# POWER.net
KiCad netlist of a schematic drawn in Altium Designer
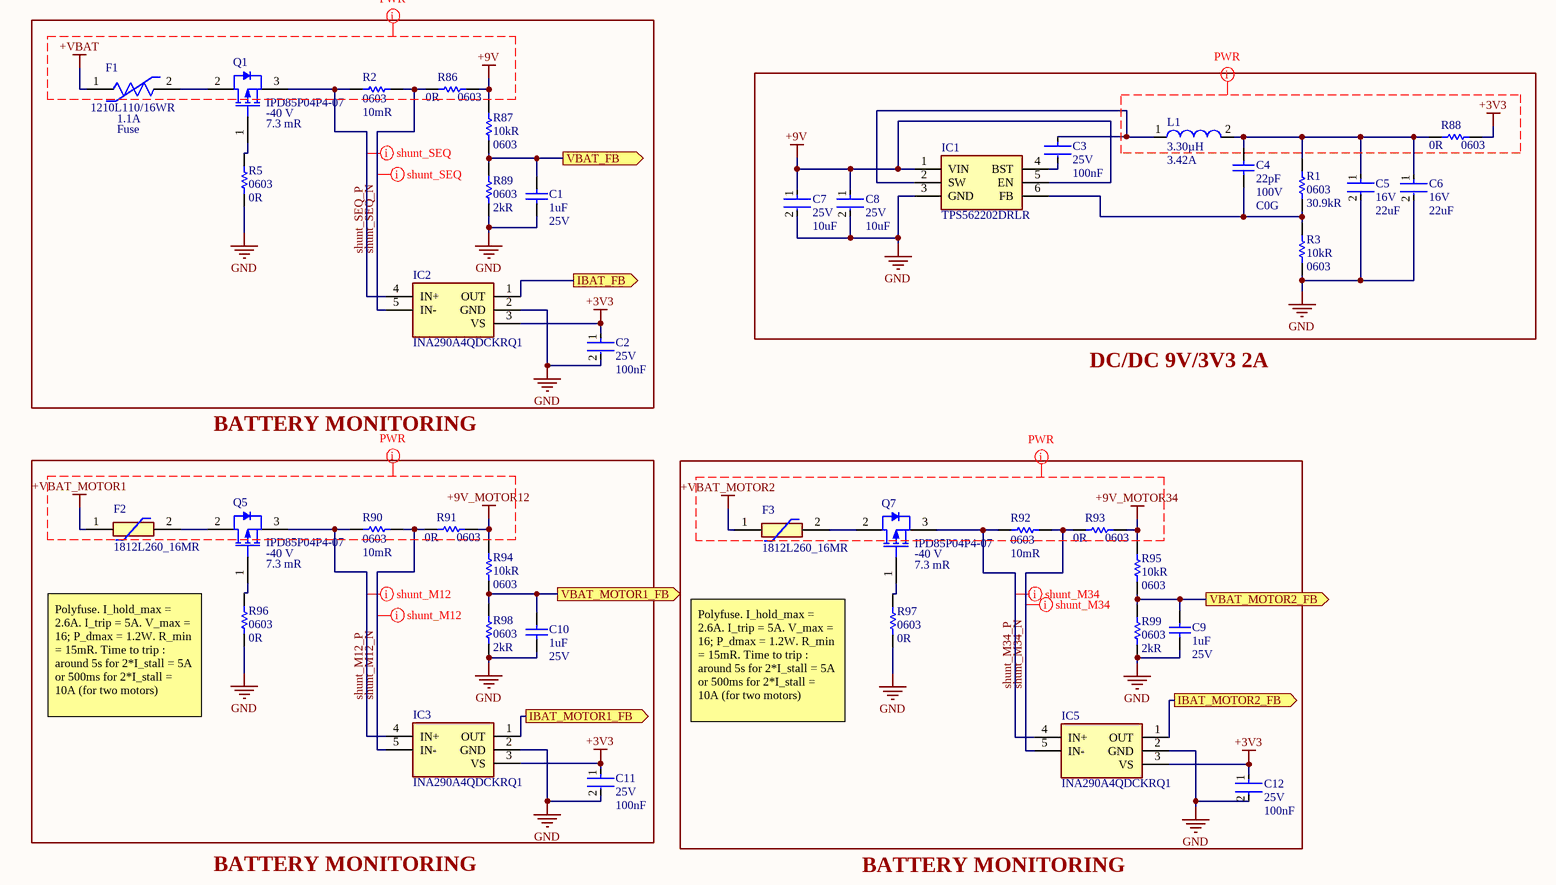
[diagram p0: POWER.SchDoc]

(export (version "E")
  (design (tool "Eeschema 10.0.6"))
  (components
    (comp (ref "C1")
      (value "C0603C105K3PAC7867")
      (footprint "CAPC1608X90X35LL15T15")
      (fields
        (field (name "MANUFACTURER") "Kemet")
        (field (name "MANUFACTURER PART NUMBER") "C0603C105K3PACTU")
        (field (name "CAPACITANCE") "1uF")
        (field (name "TOLERANCE") "10%")
        (field (name "VOLTAGE RATING (DC)") "25V")
      )
      (libsource (lib "Altium Content Vault") (part "CAP"))
    )
    (comp (ref "C2")
      (value "CGA3E2X7R1E104K080AA")
      (footprint "FP-CGA3E-0_3-0_1-MFG")
      (description "Cap Ceramic 100nF 25V X7R 10% Pad SMD 0603 +125°C Automotive T/R")
      (fields
        (field (name "VOLTAGE RATING (DC)") "25V")
        (field (name "CAPACITANCE") "100nF")
        (field (name "TOLERANCE") "10%")
        (field (name "MANUFACTURER") "TDK")
      )
      (libsource (lib "Altium Content Vault") (part "b4654b650e69147ec39a6b967a45e02"))
    )
    (comp (ref "C3")
      (value "CGA3E2X7R1E104K080AA")
      (footprint "FP-CGA3E-0_3-0_1-MFG")
      (description "Cap Ceramic 100nF 25V X7R 10% Pad SMD 0603 +125°C Automotive T/R")
      (fields
        (field (name "VOLTAGE RATING (DC)") "25V")
        (field (name "CAPACITANCE") "100nF")
        (field (name "TOLERANCE") "10%")
        (field (name "MANUFACTURER") "TDK")
      )
      (libsource (lib "") (part "b4654b650e69147ec39a6b967a45e02_1"))
    )
    (comp (ref "C4")
      (value "GRM1885C2A220JA01D")
      (footprint "CAPC1608X90X35NL10T15")
      (fields
        (field (name "MANUFACTURER") "Murata")
        (field (name "CAPACITANCE") "22pF")
        (field (name "TOLERANCE") "5%")
        (field (name "VOLTAGE RATING (DC)") "100V")
        (field (name "DIELECTRIC") "C0G")
        (field (name "VOLTAGE") "100V")
      )
      (libsource (lib "Altium Content Vault") (part "CAP"))
    )
    (comp (ref "C5")
      (value "C2012X5R1C226K125AC")
      (footprint "FP-C2012-125-MFG")
      (description "CAP CER 22UF 16V X5R 0805")
      (fields
        (field (name "MANUFACTURER") "TDK")
        (field (name "OCTOPART") "https://octopart.com/c2012x5r1c226k125ac-tdk-25947713")
        (field (name "VOLTAGE RATING") "16V")
        (field (name "CAPACITANCE") "22uF")
      )
      (libsource (lib "Altium Content Vault") (part "11868f565c42a9108669ba33697ecf6"))
    )
    (comp (ref "C6")
      (value "C2012X5R1C226K125AC")
      (footprint "FP-C2012-125-MFG")
      (description "CAP CER 22UF 16V X5R 0805")
      (fields
        (field (name "MANUFACTURER") "TDK")
        (field (name "OCTOPART") "https://octopart.com/c2012x5r1c226k125ac-tdk-25947713")
        (field (name "VOLTAGE RATING") "16V")
        (field (name "CAPACITANCE") "22uF")
      )
      (libsource (lib "Altium Content Vault") (part "11868f565c42a9108669ba33697ecf6"))
    )
    (comp (ref "C7")
      (value "C2012X5R1E106K125AB")
      (footprint "FP-C2012-125-0_2-IPC_B")
      (description "Multilayer Ceramic Capacitors 10μF ±10% 25V X5R SMD 0805")
      (fields
        (field (name "VOLTAGE") "25V")
        (field (name "VOLTAGE RATING (DC)") "25V")
        (field (name "TOLERANCE") "10%")
        (field (name "CAPACITANCE") "10uF")
      )
      (libsource (lib "Altium Content Vault") (part "b4654b650e69147ec39a6b967a45e02"))
    )
    (comp (ref "C8")
      (value "C2012X5R1E106K125AB")
      (footprint "FP-C2012-125-0_2-IPC_B")
      (description "Multilayer Ceramic Capacitors 10μF ±10% 25V X5R SMD 0805")
      (fields
        (field (name "VOLTAGE") "25V")
        (field (name "VOLTAGE RATING (DC)") "25V")
        (field (name "TOLERANCE") "10%")
        (field (name "CAPACITANCE") "10uF")
      )
      (libsource (lib "Altium Content Vault") (part "b4654b650e69147ec39a6b967a45e02"))
    )
    (comp (ref "C9")
      (value "C0603C105K3PAC7867")
      (footprint "CAPC1608X90X35LL15T15")
      (fields
        (field (name "MANUFACTURER") "Kemet")
        (field (name "MANUFACTURER PART NUMBER") "C0603C105K3PACTU")
        (field (name "CAPACITANCE") "1uF")
        (field (name "TOLERANCE") "10%")
        (field (name "VOLTAGE RATING (DC)") "25V")
      )
      (libsource (lib "Altium Content Vault") (part "CAP"))
    )
    (comp (ref "C10")
      (value "C0603C105K3PAC7867")
      (footprint "CAPC1608X90X35LL15T15")
      (fields
        (field (name "MANUFACTURER") "Kemet")
        (field (name "MANUFACTURER PART NUMBER") "C0603C105K3PACTU")
        (field (name "CAPACITANCE") "1uF")
        (field (name "TOLERANCE") "10%")
        (field (name "VOLTAGE RATING (DC)") "25V")
      )
      (libsource (lib "Altium Content Vault") (part "CAP"))
    )
    (comp (ref "C11")
      (value "CGA3E2X7R1E104K080AA")
      (footprint "FP-CGA3E-0_3-0_1-MFG")
      (description "Cap Ceramic 100nF 25V X7R 10% Pad SMD 0603 +125°C Automotive T/R")
      (fields
        (field (name "VOLTAGE RATING (DC)") "25V")
        (field (name "CAPACITANCE") "100nF")
        (field (name "TOLERANCE") "10%")
        (field (name "MANUFACTURER") "TDK")
      )
      (libsource (lib "Altium Content Vault") (part "b4654b650e69147ec39a6b967a45e02"))
    )
    (comp (ref "C12")
      (value "CGA3E2X7R1E104K080AA")
      (footprint "FP-CGA3E-0_3-0_1-MFG")
      (description "Cap Ceramic 100nF 25V X7R 10% Pad SMD 0603 +125°C Automotive T/R")
      (fields
        (field (name "VOLTAGE RATING (DC)") "25V")
        (field (name "CAPACITANCE") "100nF")
        (field (name "TOLERANCE") "10%")
        (field (name "MANUFACTURER") "TDK")
      )
      (libsource (lib "Altium Content Vault") (part "b4654b650e69147ec39a6b967a45e02"))
    )
    (comp (ref "F1")
      (value "1210L110/16WR")
      (footprint "FP-1210L110-16WR-MFG")
      (description "PTC RESET FUSE 16V 1.1A 1210")
      (fields
        (field (name "HOLD CURRENT") "1.1A")
        (field (name "CATEGORY") "Fuse")
        (field (name "OCTOPART") "https://octopart.com/1210l110%2F16wr-littelfuse-28867107")
        (field (name "MANUFACTURER") "Littelfuse Inc")
      )
      (libsource (lib "Altium Content Vault") (part "1c6d77a0208143737455a0c7eb396be"))
    )
    (comp (ref "F2")
      (value "1812L260_16MR")
      (footprint "SamacSys:1812L010DR")
      (description "Resettable Fuse")
      (fields
        (field (name "MANUFACTURER_PART_NUMBER") "1812L260/16MR")
        (field (name "MOUSER PART NUMBER") "576-1812L260/16MR")
      )
      (libsource (lib "*") (part "1812L260_16MR"))
    )
    (comp (ref "F3")
      (value "1812L260_16MR")
      (footprint "SamacSys:1812L010DR")
      (description "Resettable Fuse")
      (fields
        (field (name "MANUFACTURER_PART_NUMBER") "1812L260/16MR")
        (field (name "MOUSER PART NUMBER") "576-1812L260/16MR")
      )
      (libsource (lib "*") (part "1812L260_16MR"))
    )
    (comp (ref "IC1")
      (value "TPS562202DRLR")
      (footprint "SamacSys:SOTFL50P160X60-6N")
      (description "Integrated Circuit")
      (fields (field (name "MOUSER PART NUMBER") "595-TPS562202DRLR"))
      (libsource (lib "*") (part "TPS562202DRLR"))
    )
    (comp (ref "IC2")
      (value "INA290A4QDCKRQ1")
      (footprint "SamacSys:SOT65P210X110-5N")
      (description "Integrated Circuit")
      (fields (field (name "MOUSER PART NUMBER") "595-INA290A4QDCKRQ1"))
      (libsource (lib "*") (part "INA290A4QDCKRQ1"))
    )
    (comp (ref "IC3")
      (value "INA290A4QDCKRQ1")
      (footprint "SamacSys:SOT65P210X110-5N")
      (description "Integrated Circuit")
      (fields (field (name "MOUSER PART NUMBER") "595-INA290A4QDCKRQ1"))
      (libsource (lib "*") (part "INA290A4QDCKRQ1"))
    )
    (comp (ref "IC5")
      (value "INA290A4QDCKRQ1")
      (footprint "SamacSys:SOT65P210X110-5N")
      (description "Integrated Circuit")
      (fields (field (name "MOUSER PART NUMBER") "595-INA290A4QDCKRQ1"))
      (libsource (lib "*") (part "INA290A4QDCKRQ1"))
    )
    (comp (ref "L1")
      (value "7447789003")
      (footprint "WE-PD-S-PB")
      (description "SMD-Shielded Power Inductor WE-PD, L=3.30 µH")
      (fields
        (field (name "INDUCTANCE") "3.30µH")
        (field (name "MANUFACTURER") "Wuerth Elektronik")
        (field (name "TOLERANCE") "20%")
        (field (name "CURRENT RATING") "3.42A")
      )
      (libsource (lib "Altium Content Vault") (part "PAS-IND-INDUCTOR-2"))
    )
    (comp (ref "Q1")
      (value "IPD85P04P4-07")
      (footprint "INF-PG-TO252-3-313_L")
      (description "OptiMOS-P2 Power-Transistor, -40 V VDS, -85 A ID, PG-TO252-3-313, Reel, Green")
      (fields
        (field (name "VDS (MAX)") "-40 V")
        (field (name "RDS (ON) (MAX) (@10V)") "7.3 mR")
        (field (name "MANUFACTURER") "Infineon")
      )
      (libsource (lib "Altium Content Vault") (part "INF-MOSFET-P-3"))
    )
    (comp (ref "Q5")
      (value "IPD85P04P4-07")
      (footprint "INF-PG-TO252-3-313_L")
      (description "OptiMOS-P2 Power-Transistor, -40 V VDS, -85 A ID, PG-TO252-3-313, Reel, Green")
      (fields
        (field (name "VDS (MAX)") "-40 V")
        (field (name "RDS (ON) (MAX) (@10V)") "7.3 mR")
        (field (name "MANUFACTURER") "Infineon")
      )
      (libsource (lib "Altium Content Vault") (part "INF-MOSFET-P-3"))
    )
    (comp (ref "Q7")
      (value "IPD85P04P4-07")
      (footprint "INF-PG-TO252-3-313_L")
      (description "OptiMOS-P2 Power-Transistor, -40 V VDS, -85 A ID, PG-TO252-3-313, Reel, Green")
      (fields
        (field (name "VDS (MAX)") "-40 V")
        (field (name "RDS (ON) (MAX) (@10V)") "7.3 mR")
        (field (name "MANUFACTURER") "Infineon")
      )
      (libsource (lib "Altium Content Vault") (part "INF-MOSFET-P-3"))
    )
    (comp (ref "R1")
      (value "RC0603FR-0730K9L")
      (footprint "RESC1608X55X25NL10T15")
      (fields
        (field (name "MANUFACTURER") "Yageo")
        (field (name "CASE CODE (IMPERIAL)") "0603")
        (field (name "TOLERANCE") "1%")
        (field (name "RESISTANCE") "30.9kR")
      )
      (libsource (lib "Altium Content Vault") (part "RES"))
    )
    (comp (ref "R2")
      (value "WSL0603R0100FEA")
      (footprint "RESC1508X46X38ML25T25")
      (fields
        (field (name "MANUFACTURER") "Vishay Dale")
        (field (name "CASE CODE (IMPERIAL)") "0603")
        (field (name "TOLERANCE") "1%")
        (field (name "RESISTANCE") "10mR")
      )
      (libsource (lib "Altium Content Vault") (part "RES"))
    )
    (comp (ref "R3")
      (value "ERJ3EKF1002V")
      (footprint "RESC1609X55X30LL15T15")
      (description "Chip Resistor, 10 KOhm, +/- 1%, 0.1 W, -55 to 155 degC, 0603 (1608 Metric), RoHS, Tape and Reel")
      (fields
        (field (name "RESISTANCE") "10kR")
        (field (name "CASE CODE (IMPERIAL)") "0603")
        (field (name "TOLERANCE") "1%")
        (field (name "MANUFACTURER") "Panasonic")
      )
      (libsource (lib "Altium Content Vault") (part "RES-2"))
    )
    (comp (ref "R5")
      (value "RC0603JR-070RL")
      (footprint "RESC1608X55X25ML10T15")
      (description "Chip Resistor, 0 Ohm, +/- 5%, 0.1 W, -55 to 155 degC, 0603 (1608 Metric), RoHS, Tape and Reel")
      (fields
        (field (name "TOLERANCE") "5%")
        (field (name "CASE CODE (IMPERIAL)") "0603")
        (field (name "RESISTANCE") "0R")
        (field (name "MANUFACTURER") "Yageo")
      )
      (libsource (lib "Altium Content Vault") (part "RES-2"))
    )
    (comp (ref "R86")
      (value "RC0603JR-070RL")
      (footprint "RESC1608X55X25ML10T15")
      (description "Chip Resistor, 0 Ohm, +/- 5%, 0.1 W, -55 to 155 degC, 0603 (1608 Metric), RoHS, Tape and Reel")
      (fields
        (field (name "TOLERANCE") "5%")
        (field (name "CASE CODE (IMPERIAL)") "0603")
        (field (name "RESISTANCE") "0R")
        (field (name "MANUFACTURER") "Yageo")
      )
      (libsource (lib "Altium Content Vault") (part "RES-2"))
    )
    (comp (ref "R87")
      (value "ERJ3EKF1002V")
      (footprint "RESC1609X55X30LL15T15")
      (description "Chip Resistor, 10 KOhm, +/- 1%, 0.1 W, -55 to 155 degC, 0603 (1608 Metric), RoHS, Tape and Reel")
      (fields
        (field (name "RESISTANCE") "10kR")
        (field (name "CASE CODE (IMPERIAL)") "0603")
        (field (name "TOLERANCE") "1%")
        (field (name "MANUFACTURER") "Panasonic")
      )
      (libsource (lib "Altium Content Vault") (part "RES-2"))
    )
    (comp (ref "R88")
      (value "RC0603JR-070RL")
      (footprint "RESC1608X55X25ML10T15")
      (description "Chip Resistor, 0 Ohm, +/- 5%, 0.1 W, -55 to 155 degC, 0603 (1608 Metric), RoHS, Tape and Reel")
      (fields
        (field (name "TOLERANCE") "5%")
        (field (name "CASE CODE (IMPERIAL)") "0603")
        (field (name "RESISTANCE") "0R")
        (field (name "MANUFACTURER") "Yageo")
      )
      (libsource (lib "Altium Content Vault") (part "RES-2"))
    )
    (comp (ref "R89")
      (value "ERJ-3EKF2001V")
      (footprint "RESC1608X55X30ML15T15")
      (fields
        (field (name "MANUFACTURER") "Panasonic")
        (field (name "CASE CODE (IMPERIAL)") "0603")
        (field (name "RESISTANCE") "2kR")
        (field (name "TOLERANCE") "1%")
      )
      (libsource (lib "Altium Content Vault") (part "RES"))
    )
    (comp (ref "R90")
      (value "WSL0603R0100FEA")
      (footprint "RESC1508X46X38ML25T25")
      (fields
        (field (name "MANUFACTURER") "Vishay Dale")
        (field (name "CASE CODE (IMPERIAL)") "0603")
        (field (name "TOLERANCE") "1%")
        (field (name "RESISTANCE") "10mR")
      )
      (libsource (lib "Altium Content Vault") (part "RES"))
    )
    (comp (ref "R91")
      (value "RC0603JR-070RL")
      (footprint "RESC1608X55X25ML10T15")
      (description "Chip Resistor, 0 Ohm, +/- 5%, 0.1 W, -55 to 155 degC, 0603 (1608 Metric), RoHS, Tape and Reel")
      (fields
        (field (name "TOLERANCE") "5%")
        (field (name "CASE CODE (IMPERIAL)") "0603")
        (field (name "RESISTANCE") "0R")
        (field (name "MANUFACTURER") "Yageo")
      )
      (libsource (lib "Altium Content Vault") (part "RES-2"))
    )
    (comp (ref "R92")
      (value "WSL0603R0100FEA")
      (footprint "RESC1508X46X38ML25T25")
      (fields
        (field (name "MANUFACTURER") "Vishay Dale")
        (field (name "CASE CODE (IMPERIAL)") "0603")
        (field (name "TOLERANCE") "1%")
        (field (name "RESISTANCE") "10mR")
      )
      (libsource (lib "Altium Content Vault") (part "RES"))
    )
    (comp (ref "R93")
      (value "RC0603JR-070RL")
      (footprint "RESC1608X55X25ML10T15")
      (description "Chip Resistor, 0 Ohm, +/- 5%, 0.1 W, -55 to 155 degC, 0603 (1608 Metric), RoHS, Tape and Reel")
      (fields
        (field (name "TOLERANCE") "5%")
        (field (name "CASE CODE (IMPERIAL)") "0603")
        (field (name "RESISTANCE") "0R")
        (field (name "MANUFACTURER") "Yageo")
      )
      (libsource (lib "Altium Content Vault") (part "RES-2"))
    )
    (comp (ref "R94")
      (value "ERJ3EKF1002V")
      (footprint "RESC1609X55X30LL15T15")
      (description "Chip Resistor, 10 KOhm, +/- 1%, 0.1 W, -55 to 155 degC, 0603 (1608 Metric), RoHS, Tape and Reel")
      (fields
        (field (name "RESISTANCE") "10kR")
        (field (name "CASE CODE (IMPERIAL)") "0603")
        (field (name "TOLERANCE") "1%")
        (field (name "MANUFACTURER") "Panasonic")
      )
      (libsource (lib "Altium Content Vault") (part "RES-2"))
    )
    (comp (ref "R95")
      (value "ERJ3EKF1002V")
      (footprint "RESC1609X55X30LL15T15")
      (description "Chip Resistor, 10 KOhm, +/- 1%, 0.1 W, -55 to 155 degC, 0603 (1608 Metric), RoHS, Tape and Reel")
      (fields
        (field (name "RESISTANCE") "10kR")
        (field (name "CASE CODE (IMPERIAL)") "0603")
        (field (name "TOLERANCE") "1%")
        (field (name "MANUFACTURER") "Panasonic")
      )
      (libsource (lib "Altium Content Vault") (part "RES-2"))
    )
    (comp (ref "R96")
      (value "RC0603JR-070RL")
      (footprint "RESC1608X55X25ML10T15")
      (description "Chip Resistor, 0 Ohm, +/- 5%, 0.1 W, -55 to 155 degC, 0603 (1608 Metric), RoHS, Tape and Reel")
      (fields
        (field (name "TOLERANCE") "5%")
        (field (name "CASE CODE (IMPERIAL)") "0603")
        (field (name "RESISTANCE") "0R")
        (field (name "MANUFACTURER") "Yageo")
      )
      (libsource (lib "Altium Content Vault") (part "RES-2"))
    )
    (comp (ref "R97")
      (value "RC0603JR-070RL")
      (footprint "RESC1608X55X25ML10T15")
      (description "Chip Resistor, 0 Ohm, +/- 5%, 0.1 W, -55 to 155 degC, 0603 (1608 Metric), RoHS, Tape and Reel")
      (fields
        (field (name "TOLERANCE") "5%")
        (field (name "CASE CODE (IMPERIAL)") "0603")
        (field (name "RESISTANCE") "0R")
        (field (name "MANUFACTURER") "Yageo")
      )
      (libsource (lib "Altium Content Vault") (part "RES-2"))
    )
    (comp (ref "R98")
      (value "ERJ-3EKF2001V")
      (footprint "RESC1608X55X30ML15T15")
      (fields
        (field (name "MANUFACTURER") "Panasonic")
        (field (name "CASE CODE (IMPERIAL)") "0603")
        (field (name "RESISTANCE") "2kR")
        (field (name "TOLERANCE") "1%")
      )
      (libsource (lib "Altium Content Vault") (part "RES"))
    )
    (comp (ref "R99")
      (value "ERJ-3EKF2001V")
      (footprint "RESC1608X55X30ML15T15")
      (fields
        (field (name "MANUFACTURER") "Panasonic")
        (field (name "CASE CODE (IMPERIAL)") "0603")
        (field (name "RESISTANCE") "2kR")
        (field (name "TOLERANCE") "1%")
      )
      (libsource (lib "Altium Content Vault") (part "RES"))
    )
  )
  (nets
    (net (code "1") (name "+3V3") (class "Default")
      (node (ref "C11") (pin "1") (pinfunction "1_1") (pintype "passive"))
      (node (ref "C12") (pin "1") (pinfunction "1_1") (pintype "passive"))
      (node (ref "C2") (pin "1") (pinfunction "1_1") (pintype "passive"))
      (node (ref "IC2") (pin "3") (pinfunction "VS_3") (pintype "passive"))
      (node (ref "IC3") (pin "3") (pinfunction "VS_3") (pintype "passive"))
      (node (ref "IC5") (pin "3") (pinfunction "VS_3") (pintype "passive"))
      (node (ref "R88") (pin "2") (pinfunction "2_2") (pintype "passive"))
    )
    (net (code "2") (name "+9V") (class "Default")
      (node (ref "C7") (pin "1") (pinfunction "1_1") (pintype "passive"))
      (node (ref "C8") (pin "1") (pinfunction "1_1") (pintype "passive"))
      (node (ref "IC1") (pin "1") (pinfunction "VIN_1") (pintype "passive"))
      (node (ref "IC1") (pin "5") (pinfunction "EN_5") (pintype "passive"))
      (node (ref "R86") (pin "2") (pinfunction "2_2") (pintype "passive"))
      (node (ref "R87") (pin "2") (pinfunction "2_2") (pintype "passive"))
    )
    (net (code "3") (name "+9V_MOTOR12") (class "Default")
      (node (ref "R91") (pin "2") (pinfunction "2_2") (pintype "passive"))
      (node (ref "R94") (pin "2") (pinfunction "2_2") (pintype "passive"))
    )
    (net (code "4") (name "+9V_MOTOR34") (class "Default")
      (node (ref "R93") (pin "2") (pinfunction "2_2") (pintype "passive"))
      (node (ref "R95") (pin "2") (pinfunction "2_2") (pintype "passive"))
    )
    (net (code "5") (name "+VBAT") (class "Default")
      (node (ref "F1") (pin "1") (pinfunction "1_1") (pintype "passive"))
    )
    (net (code "6") (name "+VBAT_MOTOR1") (class "Default")
      (node (ref "F2") (pin "1") (pinfunction "1_1") (pintype "passive"))
    )
    (net (code "7") (name "+VBAT_MOTOR2") (class "Default")
      (node (ref "F3") (pin "1") (pinfunction "1_1") (pintype "passive"))
    )
    (net (code "8") (name "/IBAT_FB") (class "Default")
      (node (ref "IC2") (pin "1") (pinfunction "OUT_1") (pintype "passive"))
    )
    (net (code "9") (name "/IBAT_MOTOR1_FB") (class "Default")
      (node (ref "IC3") (pin "1") (pinfunction "OUT_1") (pintype "passive"))
    )
    (net (code "10") (name "/IBAT_MOTOR2_FB") (class "Default")
      (node (ref "IC5") (pin "1") (pinfunction "OUT_1") (pintype "passive"))
    )
    (net (code "11") (name "/VBAT_FB") (class "Default")
      (node (ref "C1") (pin "2") (pinfunction "2_2") (pintype "passive"))
      (node (ref "R87") (pin "1") (pinfunction "1_1") (pintype "passive"))
      (node (ref "R89") (pin "2") (pinfunction "2_2") (pintype "passive"))
    )
    (net (code "12") (name "/VBAT_MOTOR1_FB") (class "Default")
      (node (ref "C10") (pin "2") (pinfunction "2_2") (pintype "passive"))
      (node (ref "R94") (pin "1") (pinfunction "1_1") (pintype "passive"))
      (node (ref "R98") (pin "2") (pinfunction "2_2") (pintype "passive"))
    )
    (net (code "13") (name "/VBAT_MOTOR2_FB") (class "Default")
      (node (ref "C9") (pin "2") (pinfunction "2_2") (pintype "passive"))
      (node (ref "R95") (pin "1") (pinfunction "1_1") (pintype "passive"))
      (node (ref "R99") (pin "2") (pinfunction "2_2") (pintype "passive"))
    )
    (net (code "14") (name "/shunt_M12_N") (class "Default")
      (node (ref "IC3") (pin "5") (pinfunction "IN-_5") (pintype "passive"))
      (node (ref "R90") (pin "2") (pinfunction "2_2") (pintype "passive"))
      (node (ref "R91") (pin "1") (pinfunction "1_1") (pintype "passive"))
    )
    (net (code "15") (name "/shunt_M12_P") (class "Default")
      (node (ref "IC3") (pin "4") (pinfunction "IN+_4") (pintype "passive"))
      (node (ref "Q5") (pin "3") (pinfunction "SOURCE_3") (pintype "passive"))
      (node (ref "R90") (pin "1") (pinfunction "1_1") (pintype "passive"))
    )
    (net (code "16") (name "/shunt_M34_N") (class "Default")
      (node (ref "IC5") (pin "5") (pinfunction "IN-_5") (pintype "passive"))
      (node (ref "R92") (pin "2") (pinfunction "2_2") (pintype "passive"))
      (node (ref "R93") (pin "1") (pinfunction "1_1") (pintype "passive"))
    )
    (net (code "17") (name "/shunt_M34_P") (class "Default")
      (node (ref "IC5") (pin "4") (pinfunction "IN+_4") (pintype "passive"))
      (node (ref "Q7") (pin "3") (pinfunction "SOURCE_3") (pintype "passive"))
      (node (ref "R92") (pin "1") (pinfunction "1_1") (pintype "passive"))
    )
    (net (code "18") (name "/shunt_SEQ_N") (class "Default")
      (node (ref "IC2") (pin "5") (pinfunction "IN-_5") (pintype "passive"))
      (node (ref "R2") (pin "2") (pinfunction "2_2") (pintype "passive"))
      (node (ref "R86") (pin "1") (pinfunction "1_1") (pintype "passive"))
    )
    (net (code "19") (name "/shunt_SEQ_P") (class "Default")
      (node (ref "IC2") (pin "4") (pinfunction "IN+_4") (pintype "passive"))
      (node (ref "Q1") (pin "3") (pinfunction "SOURCE_3") (pintype "passive"))
      (node (ref "R2") (pin "1") (pinfunction "1_1") (pintype "passive"))
    )
    (net (code "20") (name "GND") (class "Default")
      (node (ref "C1") (pin "1") (pinfunction "1_1") (pintype "passive"))
      (node (ref "C10") (pin "1") (pinfunction "1_1") (pintype "passive"))
      (node (ref "C11") (pin "2") (pinfunction "2_2") (pintype "passive"))
      (node (ref "C12") (pin "2") (pinfunction "2_2") (pintype "passive"))
      (node (ref "C2") (pin "2") (pinfunction "2_2") (pintype "passive"))
      (node (ref "C5") (pin "2") (pinfunction "2_2") (pintype "passive"))
      (node (ref "C6") (pin "2") (pinfunction "2_2") (pintype "passive"))
      (node (ref "C7") (pin "2") (pinfunction "2_2") (pintype "passive"))
      (node (ref "C8") (pin "2") (pinfunction "2_2") (pintype "passive"))
      (node (ref "C9") (pin "1") (pinfunction "1_1") (pintype "passive"))
      (node (ref "IC1") (pin "3") (pinfunction "GND_3") (pintype "passive"))
      (node (ref "IC2") (pin "2") (pinfunction "GND_2") (pintype "passive"))
      (node (ref "IC3") (pin "2") (pinfunction "GND_2") (pintype "passive"))
      (node (ref "IC5") (pin "2") (pinfunction "GND_2") (pintype "passive"))
      (node (ref "R3") (pin "1") (pinfunction "1_1") (pintype "passive"))
      (node (ref "R5") (pin "1") (pinfunction "1_1") (pintype "passive"))
      (node (ref "R89") (pin "1") (pinfunction "1_1") (pintype "passive"))
      (node (ref "R96") (pin "1") (pinfunction "1_1") (pintype "passive"))
      (node (ref "R97") (pin "1") (pinfunction "1_1") (pintype "passive"))
      (node (ref "R98") (pin "1") (pinfunction "1_1") (pintype "passive"))
      (node (ref "R99") (pin "1") (pinfunction "1_1") (pintype "passive"))
    )
    (net (code "21") (name "Net-(C4-Pad2)") (class "Default")
      (node (ref "C4") (pin "2") (pinfunction "2_2") (pintype "passive"))
      (node (ref "C5") (pin "1") (pinfunction "1_1") (pintype "passive"))
      (node (ref "C6") (pin "1") (pinfunction "1_1") (pintype "passive"))
      (node (ref "L1") (pin "2") (pinfunction "2_2") (pintype "passive"))
      (node (ref "R1") (pin "2") (pinfunction "2_2") (pintype "passive"))
      (node (ref "R88") (pin "1") (pinfunction "1_1") (pintype "passive"))
    )
    (net (code "22") (name "Net-(IC1-BST)") (class "Default")
      (node (ref "C3") (pin "2") (pinfunction "2_2") (pintype "passive"))
      (node (ref "IC1") (pin "4") (pinfunction "BST_4") (pintype "passive"))
    )
    (net (code "23") (name "Net-(IC1-FB)") (class "Default")
      (node (ref "C4") (pin "1") (pinfunction "1_1") (pintype "passive"))
      (node (ref "IC1") (pin "6") (pinfunction "FB_6") (pintype "passive"))
      (node (ref "R1") (pin "1") (pinfunction "1_1") (pintype "passive"))
      (node (ref "R3") (pin "2") (pinfunction "2_2") (pintype "passive"))
    )
    (net (code "24") (name "Net-(IC1-SW)") (class "Default")
      (node (ref "C3") (pin "1") (pinfunction "1_1") (pintype "passive"))
      (node (ref "IC1") (pin "2") (pinfunction "SW_2") (pintype "passive"))
      (node (ref "L1") (pin "1") (pinfunction "1_1") (pintype "passive"))
    )
    (net (code "25") (name "Net-(Q1-DRAIN)") (class "Default")
      (node (ref "F1") (pin "2") (pinfunction "2_2") (pintype "passive"))
      (node (ref "Q1") (pin "2") (pinfunction "DRAIN_2") (pintype "passive"))
    )
    (net (code "26") (name "Net-(Q1-GATE)") (class "Default")
      (node (ref "Q1") (pin "1") (pinfunction "GATE_1") (pintype "passive"))
      (node (ref "R5") (pin "2") (pinfunction "2_2") (pintype "passive"))
    )
    (net (code "27") (name "Net-(Q5-DRAIN)") (class "Default")
      (node (ref "F2") (pin "2") (pinfunction "2_2") (pintype "passive"))
      (node (ref "Q5") (pin "2") (pinfunction "DRAIN_2") (pintype "passive"))
    )
    (net (code "28") (name "Net-(Q5-GATE)") (class "Default")
      (node (ref "Q5") (pin "1") (pinfunction "GATE_1") (pintype "passive"))
      (node (ref "R96") (pin "2") (pinfunction "2_2") (pintype "passive"))
    )
    (net (code "29") (name "Net-(Q7-DRAIN)") (class "Default")
      (node (ref "F3") (pin "2") (pinfunction "2_2") (pintype "passive"))
      (node (ref "Q7") (pin "2") (pinfunction "DRAIN_2") (pintype "passive"))
    )
    (net (code "30") (name "Net-(Q7-GATE)") (class "Default")
      (node (ref "Q7") (pin "1") (pinfunction "GATE_1") (pintype "passive"))
      (node (ref "R97") (pin "2") (pinfunction "2_2") (pintype "passive"))
    )
  )
)
